# Base_Module.net
KiCad netlist of a schematic drawn in Altium Designer
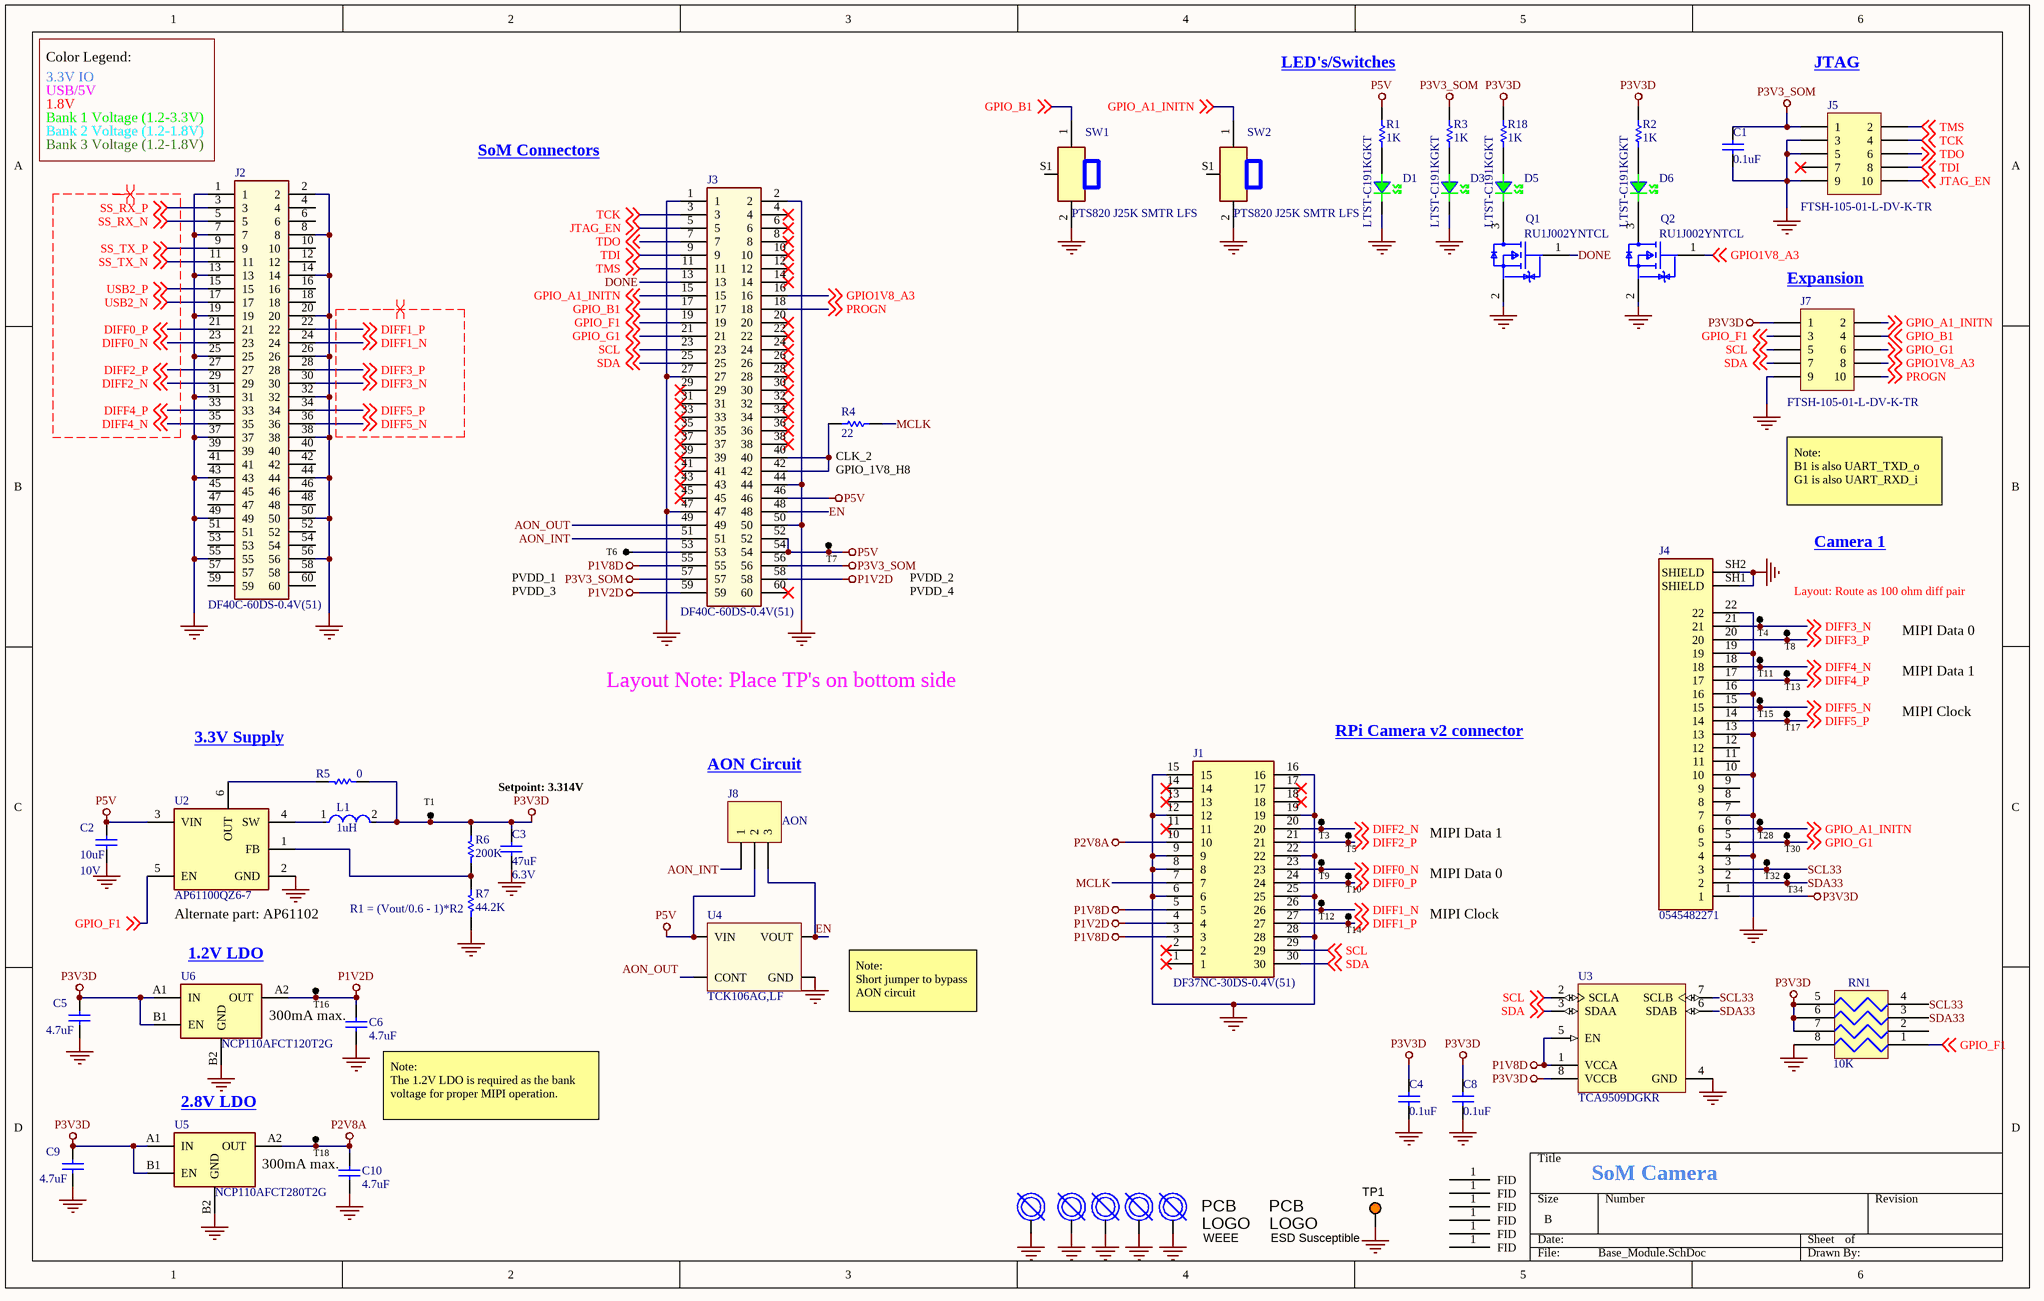
[diagram p0: Base_Module.SchDoc]

(export (version "E")
  (design (tool "Eeschema 10.0.6"))
  (components
    (comp (ref "BH1")
      (value "STANDOFF M2.5")
      (footprint "MH_Standoff_WE9774010151R")
      (description "RND STANDOFF M2.5X0.45 STEEL 1MM")
      (fields
        (field (name "MANUFACTURER") "Wurth Electronics")
        (field (name "MANUFACTURER PART NUMBER") "9774010151R")
      )
      (libsource (lib "MIPI_xlator") (part "MOUNT_HOLE"))
    )
    (comp (ref "BH2")
      (value "STANDOFF M2.5")
      (footprint "MH_Standoff_WE9774010151R")
      (description "RND STANDOFF M2.5X0.45 STEEL 1MM")
      (fields
        (field (name "MANUFACTURER") "Wurth Electronics")
        (field (name "MANUFACTURER PART NUMBER") "9774010151R")
      )
      (libsource (lib "MIPI_xlator") (part "MOUNT_HOLE"))
    )
    (comp (ref "BH3")
      (value "STANDOFF M2.5")
      (footprint "MH_Standoff_WE9774010151R")
      (description "RND STANDOFF M2.5X0.45 STEEL 1MM")
      (fields
        (field (name "MANUFACTURER") "Wurth Electronics")
        (field (name "MANUFACTURER PART NUMBER") "9774010151R")
      )
      (libsource (lib "MIPI_xlator") (part "MOUNT_HOLE"))
    )
    (comp (ref "BH4")
      (value "STANDOFF M2.5")
      (footprint "MH_Standoff_WE9774010151R")
      (description "RND STANDOFF M2.5X0.45 STEEL 1MM")
      (fields
        (field (name "MANUFACTURER") "Wurth Electronics")
        (field (name "MANUFACTURER PART NUMBER") "9774010151R")
      )
      (libsource (lib "MIPI_xlator") (part "MOUNT_HOLE"))
    )
    (comp (ref "BH5")
      (value "STANDOFF M2.5")
      (footprint "MH_3MM")
      (description "ROUND STANDOFF M2X0.4 STEEL 1MM")
      (libsource (lib "MIPI_xlator") (part "MOUNT_HOLE"))
    )
    (comp (ref "C1")
      (value "0.1uF")
      (footprint "CAPC1005X55USR")
      (description "CAP CER 0.1UF 16V X7R 0402")
      (fields
        (field (name "MANUFACTURER PART NUMBER") "CGA2B1X7R1C104K050BC")
        (field (name "MANUFACTURER") "TDK Corporation")
      )
      (libsource (lib "NX Module baseboard") (part "CAP CER 0.1UF 16V X7R 0402"))
    )
    (comp (ref "C2")
      (value "10uF")
      (footprint "CAP_0603")
      (description "CAP CER 10uF 10V X5R 0603")
      (fields
        (field (name "MANUFACTURER PART NUMBER") "GRM188R61A106ME69D")
        (field (name "MANUFACTURER") "Murata Electronics")
        (field (name "VOLTAGE") "10V")
      )
      (libsource (lib "Smart Camera") (part "Cap_1uF_X5R_10%_6V3_0402"))
    )
    (comp (ref "C3")
      (value "47uF")
      (footprint "CAP_0603")
      (description "CAP CER 47UF 6.3V X5R 0603")
      (fields
        (field (name "MANUFACTURER PART NUMBER") "GRM188R60J476ME15D")
        (field (name "MANUFACTURER") "Murata Electronics")
        (field (name "VOLTAGE") "6.3V")
      )
      (libsource (lib "Smart Camera") (part "Cap_1uF_X5R_10%_6V3_0402"))
    )
    (comp (ref "C4")
      (value "0.1uF")
      (footprint "CAPC1005X55USR")
      (description "CAP CER 0.1UF 16V X7R 0402")
      (fields
        (field (name "MANUFACTURER PART NUMBER") "CGA2B1X7R1C104K050BC")
        (field (name "MANUFACTURER") "TDK Corporation")
      )
      (libsource (lib "NX Module baseboard") (part "CAP CER 0.1UF 16V X7R 0402"))
    )
    (comp (ref "C5")
      (value "4.7uF")
      (footprint "CAPC1005X55USR")
      (description "CAP CER 4.7UF 10V X5R 0402")
      (fields
        (field (name "MANUFACTURER PART NUMBER") "C1005X5R1A475M050BC")
        (field (name "MANUFACTURER") "TDK Corporation")
      )
      (libsource (lib "NX Module baseboard") (part "CAP CER 4.7UF 10V X5R 0402"))
    )
    (comp (ref "C6")
      (value "4.7uF")
      (footprint "CAPC1005X55USR")
      (description "CAP CER 4.7UF 10V X5R 0402")
      (fields
        (field (name "MANUFACTURER PART NUMBER") "C1005X5R1A475M050BC")
        (field (name "MANUFACTURER") "TDK Corporation")
      )
      (libsource (lib "NX Module baseboard") (part "CAP CER 4.7UF 10V X5R 0402"))
    )
    (comp (ref "C8")
      (value "0.1uF")
      (footprint "CAPC1005X55USR")
      (description "CAP CER 0.1UF 16V X7R 0402")
      (fields
        (field (name "MANUFACTURER PART NUMBER") "CGA2B1X7R1C104K050BC")
        (field (name "MANUFACTURER") "TDK Corporation")
      )
      (libsource (lib "NX Module baseboard") (part "CAP CER 0.1UF 16V X7R 0402"))
    )
    (comp (ref "C9")
      (value "4.7uF")
      (footprint "CAPC1005X55USR")
      (description "CAP CER 4.7UF 10V X5R 0402")
      (fields
        (field (name "MANUFACTURER PART NUMBER") "C1005X5R1A475M050BC")
        (field (name "MANUFACTURER") "TDK Corporation")
      )
      (libsource (lib "NX Module baseboard") (part "CAP CER 4.7UF 10V X5R 0402"))
    )
    (comp (ref "C10")
      (value "4.7uF")
      (footprint "CAPC1005X55USR")
      (description "CAP CER 4.7UF 10V X5R 0402")
      (fields
        (field (name "MANUFACTURER PART NUMBER") "C1005X5R1A475M050BC")
        (field (name "MANUFACTURER") "TDK Corporation")
      )
      (libsource (lib "NX Module baseboard") (part "CAP CER 4.7UF 10V X5R 0402"))
    )
    (comp (ref "D1")
      (value "LTST-C191KGKT")
      (footprint "LED_0603")
      (description "LED GREEN CLEAR CHIP 0603 SMD")
      (fields
        (field (name "MANUFACTURER") "Lite-On Inc.")
        (field (name "MANUFACTURER PART NUMBER") "LTST-C191GKT")
      )
      (libsource (lib "Tiger_Ti180") (part "0603LED_GRN"))
    )
    (comp (ref "D3")
      (value "LTST-C191KGKT")
      (footprint "LED_0603")
      (description "LED GREEN CLEAR CHIP 0603 SMD")
      (fields
        (field (name "MANUFACTURER") "Lite-On Inc.")
        (field (name "MANUFACTURER PART NUMBER") "LTST-C191GKT")
      )
      (libsource (lib "Tiger_Ti180") (part "0603LED_GRN"))
    )
    (comp (ref "D5")
      (value "LTST-C191KGKT")
      (footprint "LED_0603")
      (description "LED GREEN CLEAR CHIP 0603 SMD")
      (fields
        (field (name "MANUFACTURER") "Lite-On Inc.")
        (field (name "MANUFACTURER PART NUMBER") "LTST-C191GKT")
      )
      (libsource (lib "Tiger_Ti180") (part "0603LED_GRN"))
    )
    (comp (ref "D6")
      (value "LTST-C191KGKT")
      (footprint "LED_0603")
      (description "LED GREEN CLEAR CHIP 0603 SMD")
      (fields
        (field (name "MANUFACTURER") "Lite-On Inc.")
        (field (name "MANUFACTURER PART NUMBER") "LTST-C191GKT")
      )
      (libsource (lib "Tiger_Ti180") (part "0603LED_GRN"))
    )
    (comp (ref "FID1") (value "~") (footprint "FID_040") (libsource (lib "MIPI_xlator") (part "FID")))
    (comp (ref "FID2") (value "~") (footprint "FID_040") (libsource (lib "MIPI_xlator") (part "FID")))
    (comp (ref "FID3") (value "~") (footprint "FID_040") (libsource (lib "MIPI_xlator") (part "FID")))
    (comp (ref "FID4") (value "~") (footprint "FID_040") (libsource (lib "MIPI_xlator") (part "FID")))
    (comp (ref "FID5") (value "~") (footprint "FID_040") (libsource (lib "MIPI_xlator") (part "FID")))
    (comp (ref "FID6") (value "~") (footprint "FID_040") (libsource (lib "MIPI_xlator") (part "FID")))
    (comp (ref "J1")
      (value "DF37NC-30DS-0.4V(51)")
      (footprint "HRS_DF37NC-30DS-0.4V(51)")
      (description "Conn Stacking RCP 30 POS 0.98mm Stack Height 0.4mm Solder ST SMD Emboss T/R")
      (fields (field (name "MANUFACTURER") "Hirose"))
      (libsource (lib "tinyCamera") (part "DF37NC-30DS-0.4V(51)"))
    )
    (comp (ref "J2")
      (value "DF40C-60DS-0.4V(51)")
      (footprint "DF40C60DS04V51")
      (description "CONN RCPT 60POS SMD GOLD")
      (fields (field (name "MANUFACTURER") "Hirose"))
      (libsource (lib "NX Module baseboard") (part "DF40C-60DS-0.4V(51)"))
    )
    (comp (ref "J3")
      (value "DF40C-60DS-0.4V(51)")
      (footprint "DF40C60DS04V51")
      (description "CONN RCPT 60POS SMD GOLD")
      (fields (field (name "MANUFACTURER") "Hirose"))
      (libsource (lib "NX Module baseboard") (part "DF40C-60DS-0.4V(51)"))
    )
    (comp (ref "J4")
      (value "0545482271")
      (footprint "MOLEX_54548-2271")
      (description "CONN FFC BOTTOM 22POS 0.50MM R/A")
      (fields (field (name "MANUFACTURER") "Molex"))
      (libsource (lib "tinyAI") (part "54548-2271"))
    )
    (comp (ref "J5")
      (value "FTSH-105-01-L-DV-K-TR")
      (footprint "FTSH-105-01-XXX-DV-K")
      (description "CONN HEADER SMD 10POS 1.27MM")
      (fields (field (name "MANUFACTURER") "Samtec Inc."))
      (libsource (lib "tinyAI") (part "HDR2X5_1.27mm"))
    )
    (comp (ref "J7")
      (value "FTSH-105-01-L-DV-K-TR")
      (footprint "FTSH-105-01-XXX-DV-K")
      (description "CONN HEADER SMD 10POS 1.27MM")
      (fields (field (name "MANUFACTURER") "Samtec Inc."))
      (libsource (lib "tinyAI") (part "HDR2X5_1.27mm"))
    )
    (comp (ref "J8")
      (value "AON")
      (footprint "HDR1X3")
      (description "CONN HEADER VERT 3POS 2.54MM")
      (fields
        (field (name "MANUFACTURER") "Wurth Electronics")
        (field (name "MANUFACTURER PART NUMBER") "61300311121")
      )
      (libsource (lib "Miscellaneous Connectors") (part "Header 3"))
    )
    (comp (ref "L1")
      (value "1uH")
      (footprint "INDC2016X100N")
      (description "FIXED IND 1UH 2.7A 57 MOHM SMD")
      (fields
        (field (name "MANUFACTURER") "Murata Electronics")
        (field (name "MANUFACTURER PART NUMBER") "DFE201610E-1R0M=P2")
      )
      (libsource (lib "Smart Camera") (part "725321dda6339637d4d059423bc1c3c"))
    )
    (comp (ref "Logo1")
      (value "WEEE")
      (footprint "WEEE_Minimum")
      (description "WEEE logo")
      (libsource (lib "MIPI_xlator") (part "Logo WEEE"))
    )
    (comp (ref "Logo2")
      (value "ESD Susceptible")
      (footprint "ESD_Overlay_Medium")
      (description "ESD Susceptible Symbol")
      (fields (field (name "PUBLISHER") "Texas Instruments") (field (name "SYMBOLCREATOR") "a0412235"))
      (libsource (lib "MIPI_xlator") (part "Logo ESD"))
    )
    (comp (ref "Q1")
      (value "RU1J002YNTCL")
      (footprint "SOT-323FL")
      (description "MOSFET N-CH 50V 0.2A UMT3F")
      (fields
        (field (name "MANUFACTURER") "Rohm")
        (field (name "OCTOPART") "https://octopart.com/ru1j002yntcl-rohm-47197697")
      )
      (libsource (lib "AiC") (part "1926738d861a973c8d722c53ec8fd09"))
    )
    (comp (ref "Q2")
      (value "RU1J002YNTCL")
      (footprint "SOT-323FL")
      (description "MOSFET N-CH 50V 0.2A UMT3F")
      (fields
        (field (name "MANUFACTURER") "Rohm")
        (field (name "OCTOPART") "https://octopart.com/ru1j002yntcl-rohm-47197697")
      )
      (libsource (lib "AiC") (part "1926738d861a973c8d722c53ec8fd09"))
    )
    (comp (ref "R1")
      (value "1K")
      (footprint "RESC1005X40USR")
      (description "RES SMD 1K OHM 1% 1/16W 0402")
      (fields
        (field (name "MANUFACTURER") "YAGEO")
        (field (name "MANUFACTURER PART NUMBER") "RC0402FR-071KL")
      )
      (libsource (lib "Tiger_Ti180") (part "RES 1K OHM 1% 1/16W 0402"))
    )
    (comp (ref "R2")
      (value "1K")
      (footprint "RESC1005X40USR")
      (description "RES SMD 1K OHM 1% 1/16W 0402")
      (fields
        (field (name "MANUFACTURER") "YAGEO")
        (field (name "MANUFACTURER PART NUMBER") "RC0402FR-071KL")
      )
      (libsource (lib "Tiger_Ti180") (part "RES 1K OHM 1% 1/16W 0402"))
    )
    (comp (ref "R3")
      (value "1K")
      (footprint "RESC1005X40USR")
      (description "RES SMD 1K OHM 1% 1/16W 0402")
      (fields
        (field (name "MANUFACTURER") "YAGEO")
        (field (name "MANUFACTURER PART NUMBER") "RC0402FR-071KL")
      )
      (libsource (lib "Tiger_Ti180") (part "RES 1K OHM 1% 1/16W 0402"))
    )
    (comp (ref "R4")
      (value "22")
      (footprint "RESC1005X40USR")
      (description "RES 22 OHM 1% 1/16W 0402")
      (fields
        (field (name "MANUFACTURER") "YAGEO")
        (field (name "MANUFACTURER PART NUMBER") "RC0402FR-0722RL")
      )
      (libsource (lib "Tiger_Ti180") (part "RES 1K OHM 1% 1/16W 0402"))
    )
    (comp (ref "R5")
      (value "0")
      (footprint "RESC1005X40USR")
      (description "RES 0 OHM JUMPER 1/16W 0402")
      (fields
        (field (name "MANUFACTURER") "Yageo")
        (field (name "MANUFACTURER PART NUMBER") "RC0402JR-070RL")
      )
      (libsource (lib "Smart Camera v2") (part "RES 0 OHM JUMPER 1/20W 0201"))
    )
    (comp (ref "R6")
      (value "200K")
      (footprint "RESC1005X40USR")
      (description "RES SMD 200K OHM 1% 1/16W 0402")
      (fields
        (field (name "MANUFACTURER") "Stackpole Electronics Inc")
        (field (name "MANUFACTURER PART NUMBER") "RMCF0402FT200K")
      )
      (libsource (lib "MCD_Temp_LBE") (part "Res_10K_1%_0402"))
    )
    (comp (ref "R7")
      (value "44.2K")
      (footprint "RESC1005X40USR")
      (description "RES SMD 44.2K OHM 1% 1/16W 0402")
      (fields
        (field (name "MANUFACTURER") "Yageo")
        (field (name "MANUFACTURER PART NUMBER") "RC0402FR-0744K2L")
      )
      (libsource (lib "MCD_Temp_LBE") (part "Res_10K_1%_0402"))
    )
    (comp (ref "R18")
      (value "1K")
      (footprint "RESC1005X40USR")
      (description "RES SMD 1K OHM 1% 1/16W 0402")
      (fields
        (field (name "MANUFACTURER") "YAGEO")
        (field (name "MANUFACTURER PART NUMBER") "RC0402FR-071KL")
      )
      (libsource (lib "Tiger_Ti180") (part "RES 1K OHM 1% 1/16W 0402"))
    )
    (comp (ref "RN1")
      (value "10K")
      (footprint "RESCAXS50P100X200X45-8NA")
      (description "Res Thick Film Array 10K Ohm 5% ±200ppm/°C ISOL 8-Pin 0804(4 X 0402) Convex SMD Automotive T/R")
      (fields
        (field (name "MANUFACTURER") "Panasonic")
        (field (name "MANUFACTURER PART NUMBER") "EXB-28V103JX")
      )
      (libsource (lib "NX Module") (part "RES ARRAY 4 RES 47K OHM 0804"))
    )
    (comp (ref "SW1")
      (value "PTS820 J25K SMTR LFS")
      (footprint "PTS820J25MSMTRLFS")
      (description "SWITCH TACTILE SPST-NO 0.05A 12V")
      (fields (field (name "MANUFACTURER") "C&K"))
      (libsource (lib "Tiger_Ti180") (part "SPST_NO"))
    )
    (comp (ref "SW2")
      (value "PTS820 J25K SMTR LFS")
      (footprint "PTS820J25MSMTRLFS")
      (description "SWITCH TACTILE SPST-NO 0.05A 12V")
      (fields (field (name "MANUFACTURER") "C&K"))
      (libsource (lib "Tiger_Ti180") (part "SPST_NO"))
    )
    (comp (ref "T1")
      (value "3V3")
      (footprint "TP 1mm")
      (description "test point")
      (libsource (lib "Smart Camera") (part "TP_S"))
    )
    (comp (ref "T3")
      (value "TP_S")
      (footprint "TP 20mil")
      (description "test point")
      (libsource (lib "AiC RVP Adapter") (part "TP_S"))
    )
    (comp (ref "T4")
      (value "TP_S")
      (footprint "TP 20mil")
      (description "test point")
      (libsource (lib "AiC RVP Adapter") (part "TP_S"))
    )
    (comp (ref "T5")
      (value "TP_S")
      (footprint "TP 20mil")
      (description "test point")
      (libsource (lib "AiC RVP Adapter") (part "TP_S"))
    )
    (comp (ref "T6")
      (value "TP_S")
      (footprint "TP 20mil")
      (description "test point")
      (libsource (lib "AiC RVP Adapter") (part "TP_S"))
    )
    (comp (ref "T7")
      (value "TP_S")
      (footprint "TP 20mil")
      (description "test point")
      (libsource (lib "AiC RVP Adapter") (part "TP_S"))
    )
    (comp (ref "T8")
      (value "TP_S")
      (footprint "TP 20mil")
      (description "test point")
      (libsource (lib "AiC RVP Adapter") (part "TP_S"))
    )
    (comp (ref "T9")
      (value "TP_S")
      (footprint "TP 20mil")
      (description "test point")
      (libsource (lib "AiC RVP Adapter") (part "TP_S"))
    )
    (comp (ref "T10")
      (value "TP_S")
      (footprint "TP 20mil")
      (description "test point")
      (libsource (lib "AiC RVP Adapter") (part "TP_S"))
    )
    (comp (ref "T11")
      (value "TP_S")
      (footprint "TP 20mil")
      (description "test point")
      (libsource (lib "AiC RVP Adapter") (part "TP_S"))
    )
    (comp (ref "T12")
      (value "TP_S")
      (footprint "TP 20mil")
      (description "test point")
      (libsource (lib "AiC RVP Adapter") (part "TP_S"))
    )
    (comp (ref "T13")
      (value "TP_S")
      (footprint "TP 20mil")
      (description "test point")
      (libsource (lib "AiC RVP Adapter") (part "TP_S"))
    )
    (comp (ref "T14")
      (value "TP_S")
      (footprint "TP 20mil")
      (description "test point")
      (libsource (lib "AiC RVP Adapter") (part "TP_S"))
    )
    (comp (ref "T15")
      (value "TP_S")
      (footprint "TP 20mil")
      (description "test point")
      (libsource (lib "AiC RVP Adapter") (part "TP_S"))
    )
    (comp (ref "T16")
      (value "TP_S")
      (footprint "TP 20mil")
      (description "test point")
      (libsource (lib "AiC RVP Adapter") (part "TP_S"))
    )
    (comp (ref "T17")
      (value "TP_S")
      (footprint "TP 20mil")
      (description "test point")
      (libsource (lib "AiC RVP Adapter") (part "TP_S"))
    )
    (comp (ref "T18")
      (value "TP_S")
      (footprint "TP 20mil")
      (description "test point")
      (libsource (lib "AiC RVP Adapter") (part "TP_S"))
    )
    (comp (ref "T28")
      (value "TP_S")
      (footprint "TP 20mil")
      (description "test point")
      (libsource (lib "AiC RVP Adapter") (part "TP_S"))
    )
    (comp (ref "T30")
      (value "TP_S")
      (footprint "TP 20mil")
      (description "test point")
      (libsource (lib "AiC RVP Adapter") (part "TP_S"))
    )
    (comp (ref "T32")
      (value "TP_S")
      (footprint "TP 1mm")
      (description "test point")
      (libsource (lib "tinyEye") (part "TP_S"))
    )
    (comp (ref "T34")
      (value "TP_S")
      (footprint "TP 1mm")
      (description "test point")
      (libsource (lib "tinyEye") (part "TP_S"))
    )
    (comp (ref "TP1")
      (value "5019")
      (footprint "TP380X203")
      (description "PC TEST POINT MINIATURE")
      (fields (field (name "MANUFACTURER") "Keystone Electronics"))
      (libsource (lib "MIPI_xlator") (part "5019"))
    )
    (comp (ref "U2")
      (value "AP61100QZ6-7")
      (footprint "SOTFL50P160X60-6N")
      (description "DC-DC CONV LV BUCK SOT563")
      (fields (field (name "MANUFACTURER") "Diodes Incorporated"))
      (libsource (lib "Smart Camera") (part "AP61100Z6-7"))
    )
    (comp (ref "U3")
      (value "TCA9509DGKR")
      (footprint "SOP65P490X110-8N")
      (description "Level-translating I2C And Smbus")
      (fields (field (name "MANUFACTURER") "Texas Instruments"))
      (libsource (lib "NX Module") (part "TI-TCA9509-MSOP_DGK-8"))
    )
    (comp (ref "U4")
      (value "TCK106AG,LF")
      (footprint "WCSP4D")
      (description "IC PWR SWITCH P-CHAN 1:1 4WCSPD")
      (fields
        (field (name "MANUFACTURER") "Toshiba")
        (field (name "COPYRIGHT") "Copyright (C) 2018 Accelerated Designs. All rights reserved")
      )
      (libsource (lib "tinyAI") (part "TCK106AG"))
    )
    (comp (ref "U5")
      (value "NCP110AFCT280T2G")
      (footprint "WLCSP4_P6XP6_ONS")
      (description "LDO Regulator, 200 mA, Low Vin, Ultra-High PSRR 2.8V, Active Discharge")
      (fields (field (name "MANUFACTURER") "ON Semiconductor"))
      (libsource (lib "Tiger_Ti180") (part "NCP110AFCT120T2G"))
    )
    (comp (ref "U6")
      (value "NCP110AFCT120T2G")
      (footprint "WLCSP4_P6XP6_ONS")
      (description "LDO Regulator, 200 mA, Low Vin, Ultra-High PSRR 1.2V, Active Discharge")
      (fields (field (name "MANUFACTURER") "ON Semiconductor"))
      (libsource (lib "Tiger_Ti180") (part "NCP110AFCT120T2G"))
    )
  )
  (nets
    (net (code "1") (name "/AON_INT") (class "Default")
      (node (ref "J3") (pin "51") (pinfunction "51_51") (pintype "passive"))
      (node (ref "J8") (pin "1") (pinfunction "1_1") (pintype "passive"))
    )
    (net (code "2") (name "/AON_OUT") (class "Default")
      (node (ref "J3") (pin "49") (pinfunction "49_49") (pintype "passive"))
      (node (ref "U4") (pin "B2") (pinfunction "CONT_B2") (pintype "passive"))
    )
    (net (code "3") (name "/DONE") (class "Default")
      (node (ref "J3") (pin "13") (pinfunction "13_13") (pintype "passive"))
      (node (ref "Q1") (pin "1") (pinfunction "G_1") (pintype "passive"))
    )
    (net (code "4") (name "/EN") (class "Default")
      (node (ref "J3") (pin "48") (pinfunction "48_48") (pintype "passive"))
      (node (ref "J8") (pin "3") (pinfunction "3_3") (pintype "passive"))
      (node (ref "U4") (pin "A1") (pinfunction "VOUT_A1") (pintype "passive"))
    )
    (net (code "5") (name "/MCLK") (class "Default")
      (node (ref "J1") (pin "7") (pinfunction "7_7") (pintype "passive"))
      (node (ref "R4") (pin "2") (pinfunction "2_2") (pintype "passive"))
    )
    (net (code "6") (name "/SCL33") (class "Default")
      (node (ref "J4") (pin "3") (pinfunction "3_3") (pintype "passive"))
      (node (ref "RN1") (pin "4") (pintype "passive"))
      (node (ref "T32") (pin "1") (pintype "passive"))
      (node (ref "U3") (pin "7") (pinfunction "SCLB_7") (pintype "bidirectional"))
    )
    (net (code "7") (name "/SDA33") (class "Default")
      (node (ref "J4") (pin "2") (pinfunction "2_2") (pintype "passive"))
      (node (ref "RN1") (pin "3") (pintype "passive"))
      (node (ref "T34") (pin "1") (pintype "passive"))
      (node (ref "U3") (pin "6") (pinfunction "SDAB_6") (pintype "bidirectional"))
    )
    (net (code "8") (name "DIFF0_N") (class "Default")
      (node (ref "J1") (pin "23") (pinfunction "23_23") (pintype "passive"))
      (node (ref "J2") (pin "23") (pinfunction "23_23") (pintype "passive"))
      (node (ref "T9") (pin "1") (pintype "passive"))
    )
    (net (code "9") (name "DIFF0_P") (class "Default")
      (node (ref "J1") (pin "24") (pinfunction "24_24") (pintype "passive"))
      (node (ref "J2") (pin "21") (pinfunction "21_21") (pintype "passive"))
      (node (ref "T10") (pin "1") (pintype "passive"))
    )
    (net (code "10") (name "DIFF1_N") (class "Default")
      (node (ref "J1") (pin "26") (pinfunction "26_26") (pintype "passive"))
      (node (ref "J2") (pin "24") (pinfunction "24_24") (pintype "passive"))
      (node (ref "T12") (pin "1") (pintype "passive"))
    )
    (net (code "11") (name "DIFF1_P") (class "Default")
      (node (ref "J1") (pin "27") (pinfunction "27_27") (pintype "passive"))
      (node (ref "J2") (pin "22") (pinfunction "22_22") (pintype "passive"))
      (node (ref "T14") (pin "1") (pintype "passive"))
    )
    (net (code "12") (name "DIFF2_N") (class "Default")
      (node (ref "J1") (pin "20") (pinfunction "20_20") (pintype "passive"))
      (node (ref "J2") (pin "29") (pinfunction "29_29") (pintype "passive"))
      (node (ref "T3") (pin "1") (pintype "passive"))
    )
    (net (code "13") (name "DIFF2_P") (class "Default")
      (node (ref "J1") (pin "21") (pinfunction "21_21") (pintype "passive"))
      (node (ref "J2") (pin "27") (pinfunction "27_27") (pintype "passive"))
      (node (ref "T5") (pin "1") (pintype "passive"))
    )
    (net (code "14") (name "DIFF3_N") (class "Default")
      (node (ref "J2") (pin "30") (pinfunction "30_30") (pintype "passive"))
      (node (ref "J4") (pin "21") (pinfunction "21_21") (pintype "passive"))
      (node (ref "T4") (pin "1") (pintype "passive"))
    )
    (net (code "15") (name "DIFF3_P") (class "Default")
      (node (ref "J2") (pin "28") (pinfunction "28_28") (pintype "passive"))
      (node (ref "J4") (pin "20") (pinfunction "20_20") (pintype "passive"))
      (node (ref "T8") (pin "1") (pintype "passive"))
    )
    (net (code "16") (name "DIFF4_N") (class "Default")
      (node (ref "J2") (pin "35") (pinfunction "35_35") (pintype "passive"))
      (node (ref "J4") (pin "18") (pinfunction "18_18") (pintype "passive"))
      (node (ref "T11") (pin "1") (pintype "passive"))
    )
    (net (code "17") (name "DIFF4_P") (class "Default")
      (node (ref "J2") (pin "33") (pinfunction "33_33") (pintype "passive"))
      (node (ref "J4") (pin "17") (pinfunction "17_17") (pintype "passive"))
      (node (ref "T13") (pin "1") (pintype "passive"))
    )
    (net (code "18") (name "DIFF5_N") (class "Default")
      (node (ref "J2") (pin "36") (pinfunction "36_36") (pintype "passive"))
      (node (ref "J4") (pin "15") (pinfunction "15_15") (pintype "passive"))
      (node (ref "T15") (pin "1") (pintype "passive"))
    )
    (net (code "19") (name "DIFF5_P") (class "Default")
      (node (ref "J2") (pin "34") (pinfunction "34_34") (pintype "passive"))
      (node (ref "J4") (pin "14") (pinfunction "14_14") (pintype "passive"))
      (node (ref "T17") (pin "1") (pintype "passive"))
    )
    (net (code "20") (name "GND") (class "Default")
      (node (ref "BH1") (pin "1") (pinfunction "1_1") (pintype "passive"))
      (node (ref "BH2") (pin "1") (pinfunction "1_1") (pintype "passive"))
      (node (ref "BH3") (pin "1") (pinfunction "1_1") (pintype "passive"))
      (node (ref "BH4") (pin "1") (pinfunction "1_1") (pintype "passive"))
      (node (ref "BH5") (pin "1") (pinfunction "1_1") (pintype "passive"))
      (node (ref "C1") (pin "1") (pinfunction "1_1") (pintype "passive"))
      (node (ref "C10") (pin "1") (pinfunction "1_1") (pintype "passive"))
      (node (ref "C2") (pin "1") (pinfunction "1_1") (pintype "passive"))
      (node (ref "C3") (pin "1") (pinfunction "1_1") (pintype "passive"))
      (node (ref "C4") (pin "1") (pinfunction "1_1") (pintype "passive"))
      (node (ref "C5") (pin "1") (pinfunction "1_1") (pintype "passive"))
      (node (ref "C6") (pin "1") (pinfunction "1_1") (pintype "passive"))
      (node (ref "C8") (pin "1") (pinfunction "1_1") (pintype "passive"))
      (node (ref "C9") (pin "1") (pinfunction "1_1") (pintype "passive"))
      (node (ref "D1") (pin "2") (pinfunction "K_2") (pintype "passive"))
      (node (ref "D3") (pin "2") (pinfunction "K_2") (pintype "passive"))
      (node (ref "J1") (pin "12") (pinfunction "12_12") (pintype "passive"))
      (node (ref "J1") (pin "15") (pinfunction "15_15") (pintype "passive"))
      (node (ref "J1") (pin "16") (pinfunction "16_16") (pintype "passive"))
      (node (ref "J1") (pin "19") (pinfunction "19_19") (pintype "passive"))
      (node (ref "J1") (pin "22") (pinfunction "22_22") (pintype "passive"))
      (node (ref "J1") (pin "25") (pinfunction "25_25") (pintype "passive"))
      (node (ref "J1") (pin "28") (pinfunction "28_28") (pintype "passive"))
      (node (ref "J1") (pin "6") (pinfunction "6_6") (pintype "passive"))
      (node (ref "J1") (pin "8") (pinfunction "8_8") (pintype "passive"))
      (node (ref "J1") (pin "9") (pinfunction "9_9") (pintype "passive"))
      (node (ref "J2") (pin "1") (pinfunction "1_1") (pintype "passive"))
      (node (ref "J2") (pin "13") (pinfunction "13_13") (pintype "passive"))
      (node (ref "J2") (pin "14") (pinfunction "14_14") (pintype "passive"))
      (node (ref "J2") (pin "19") (pinfunction "19_19") (pintype "passive"))
      (node (ref "J2") (pin "2") (pinfunction "2_2") (pintype "passive"))
      (node (ref "J2") (pin "20") (pinfunction "20_20") (pintype "passive"))
      (node (ref "J2") (pin "25") (pinfunction "25_25") (pintype "passive"))
      (node (ref "J2") (pin "26") (pinfunction "26_26") (pintype "passive"))
      (node (ref "J2") (pin "31") (pinfunction "31_31") (pintype "passive"))
      (node (ref "J2") (pin "32") (pinfunction "32_32") (pintype "passive"))
      (node (ref "J2") (pin "37") (pinfunction "37_37") (pintype "passive"))
      (node (ref "J2") (pin "38") (pinfunction "38_38") (pintype "passive"))
      (node (ref "J2") (pin "43") (pinfunction "43_43") (pintype "passive"))
      (node (ref "J2") (pin "44") (pinfunction "44_44") (pintype "passive"))
      (node (ref "J2") (pin "49") (pinfunction "49_49") (pintype "passive"))
      (node (ref "J2") (pin "50") (pinfunction "50_50") (pintype "passive"))
      (node (ref "J2") (pin "55") (pinfunction "55_55") (pintype "passive"))
      (node (ref "J2") (pin "56") (pinfunction "56_56") (pintype "passive"))
      (node (ref "J2") (pin "7") (pinfunction "7_7") (pintype "passive"))
      (node (ref "J2") (pin "8") (pinfunction "8_8") (pintype "passive"))
      (node (ref "J3") (pin "1") (pinfunction "1_1") (pintype "passive"))
      (node (ref "J3") (pin "2") (pinfunction "2_2") (pintype "passive"))
      (node (ref "J3") (pin "27") (pinfunction "27_27") (pintype "passive"))
      (node (ref "J3") (pin "44") (pinfunction "44_44") (pintype "passive"))
      (node (ref "J3") (pin "47") (pinfunction "47_47") (pintype "passive"))
      (node (ref "J3") (pin "50") (pinfunction "50_50") (pintype "passive"))
      (node (ref "J4") (pin "10") (pinfunction "10_10") (pintype "passive"))
      (node (ref "J4") (pin "13") (pinfunction "13_13") (pintype "passive"))
      (node (ref "J4") (pin "16") (pinfunction "16_16") (pintype "passive"))
      (node (ref "J4") (pin "19") (pinfunction "19_19") (pintype "passive"))
      (node (ref "J4") (pin "22") (pinfunction "22_22") (pintype "passive"))
      (node (ref "J4") (pin "4") (pinfunction "4_4") (pintype "passive"))
      (node (ref "J4") (pin "7") (pinfunction "7_7") (pintype "passive"))
      (node (ref "J4") (pin "SH1") (pinfunction "SHIELD_SH1") (pintype "passive"))
      (node (ref "J4") (pin "SH2") (pinfunction "SHIELD_SH2") (pintype "passive"))
      (node (ref "J5") (pin "3") (pinfunction "3_3") (pintype "passive"))
      (node (ref "J5") (pin "5") (pinfunction "5_5") (pintype "passive"))
      (node (ref "J5") (pin "9") (pinfunction "9_9") (pintype "passive"))
      (node (ref "J7") (pin "9") (pinfunction "9_9") (pintype "passive"))
      (node (ref "Q1") (pin "2") (pinfunction "S_2") (pintype "passive"))
      (node (ref "Q2") (pin "2") (pinfunction "S_2") (pintype "passive"))
      (node (ref "R7") (pin "1") (pinfunction "1_1") (pintype "passive"))
      (node (ref "RN1") (pin "8") (pintype "passive"))
      (node (ref "SW1") (pin "2") (pinfunction "2_2") (pintype "passive"))
      (node (ref "SW2") (pin "2") (pinfunction "2_2") (pintype "passive"))
      (node (ref "TP1") (pin "1") (pinfunction "1_1") (pintype "passive"))
      (node (ref "U2") (pin "2") (pinfunction "GND_2") (pintype "passive"))
      (node (ref "U3") (pin "4") (pinfunction "GND_4") (pintype "power_in"))
      (node (ref "U4") (pin "B1") (pinfunction "GND_B1") (pintype "passive"))
      (node (ref "U5") (pin "B2") (pinfunction "GND_B2") (pintype "passive"))
      (node (ref "U6") (pin "B2") (pinfunction "GND_B2") (pintype "passive"))
    )
    (net (code "21") (name "GPIO1V8_A3") (class "Default")
      (node (ref "J3") (pin "16") (pinfunction "16_16") (pintype "passive"))
      (node (ref "J7") (pin "8") (pinfunction "8_8") (pintype "passive"))
      (node (ref "Q2") (pin "1") (pinfunction "G_1") (pintype "passive"))
    )
    (net (code "22") (name "GPIO_A1_INITN") (class "Default")
      (node (ref "J3") (pin "15") (pinfunction "15_15") (pintype "passive"))
      (node (ref "J4") (pin "6") (pinfunction "6_6") (pintype "passive"))
      (node (ref "J7") (pin "2") (pinfunction "2_2") (pintype "passive"))
      (node (ref "SW2") (pin "1") (pinfunction "1_1") (pintype "passive"))
      (node (ref "T28") (pin "1") (pintype "passive"))
    )
    (net (code "23") (name "GPIO_B1") (class "Default")
      (node (ref "J3") (pin "17") (pinfunction "17_17") (pintype "passive"))
      (node (ref "J7") (pin "4") (pinfunction "4_4") (pintype "passive"))
      (node (ref "SW1") (pin "1") (pinfunction "1_1") (pintype "passive"))
    )
    (net (code "24") (name "GPIO_F1") (class "Default")
      (node (ref "J3") (pin "19") (pinfunction "19_19") (pintype "passive"))
      (node (ref "J7") (pin "3") (pinfunction "3_3") (pintype "passive"))
      (node (ref "RN1") (pin "1") (pintype "passive"))
      (node (ref "U2") (pin "5") (pinfunction "EN_5") (pintype "passive"))
    )
    (net (code "25") (name "GPIO_G1") (class "Default")
      (node (ref "J3") (pin "21") (pinfunction "21_21") (pintype "passive"))
      (node (ref "J4") (pin "5") (pinfunction "5_5") (pintype "passive"))
      (node (ref "J7") (pin "6") (pinfunction "6_6") (pintype "passive"))
      (node (ref "T30") (pin "1") (pintype "passive"))
    )
    (net (code "26") (name "JTAG_EN") (class "Default")
      (node (ref "J3") (pin "5") (pinfunction "5_5") (pintype "passive"))
      (node (ref "J5") (pin "10") (pinfunction "10_10") (pintype "passive"))
    )
    (net (code "27") (name "Net-(D1-A)") (class "Default")
      (node (ref "D1") (pin "1") (pinfunction "A_1") (pintype "passive"))
      (node (ref "R1") (pin "2") (pinfunction "2_2") (pintype "passive"))
    )
    (net (code "28") (name "Net-(D3-A)") (class "Default")
      (node (ref "D3") (pin "1") (pinfunction "A_1") (pintype "passive"))
      (node (ref "R3") (pin "2") (pinfunction "2_2") (pintype "passive"))
    )
    (net (code "29") (name "Net-(D5-A)") (class "Default")
      (node (ref "D5") (pin "1") (pinfunction "A_1") (pintype "passive"))
      (node (ref "R18") (pin "2") (pinfunction "2_2") (pintype "passive"))
    )
    (net (code "30") (name "Net-(D5-K)") (class "Default")
      (node (ref "D5") (pin "2") (pinfunction "K_2") (pintype "passive"))
      (node (ref "Q1") (pin "3") (pinfunction "D_3") (pintype "passive"))
    )
    (net (code "31") (name "Net-(D6-A)") (class "Default")
      (node (ref "D6") (pin "1") (pinfunction "A_1") (pintype "passive"))
      (node (ref "R2") (pin "2") (pinfunction "2_2") (pintype "passive"))
    )
    (net (code "32") (name "Net-(D6-K)") (class "Default")
      (node (ref "D6") (pin "2") (pinfunction "K_2") (pintype "passive"))
      (node (ref "Q2") (pin "3") (pinfunction "D_3") (pintype "passive"))
    )
    (net (code "33") (name "Net-(J3-Pad40)") (class "Default")
      (node (ref "J3") (pin "40") (pinfunction "40_40") (pintype "passive"))
      (node (ref "J3") (pin "42") (pinfunction "42_42") (pintype "passive"))
      (node (ref "R4") (pin "1") (pinfunction "1_1") (pintype "passive"))
    )
    (net (code "34") (name "Net-(J3-Pad53)") (class "Default")
      (node (ref "J3") (pin "53") (pinfunction "53_53") (pintype "passive"))
      (node (ref "T6") (pin "1") (pintype "passive"))
    )
    (net (code "35") (name "Net-(U2-FB)") (class "Default")
      (node (ref "R6") (pin "1") (pinfunction "1_1") (pintype "passive"))
      (node (ref "R7") (pin "2") (pinfunction "2_2") (pintype "passive"))
      (node (ref "U2") (pin "1") (pinfunction "FB_1") (pintype "passive"))
    )
    (net (code "36") (name "Net-(U2-OUT)") (class "Default")
      (node (ref "R5") (pin "2") (pinfunction "2_2") (pintype "passive"))
      (node (ref "U2") (pin "6") (pinfunction "OUT_6") (pintype "passive"))
    )
    (net (code "37") (name "Net-(U2-SW)") (class "Default")
      (node (ref "L1") (pin "1") (pinfunction "1_1") (pintype "passive"))
      (node (ref "U2") (pin "4") (pinfunction "SW_4") (pintype "passive"))
    )
    (net (code "38") (name "P1V2D") (class "Default")
      (node (ref "C6") (pin "2") (pinfunction "2_2") (pintype "passive"))
      (node (ref "J1") (pin "4") (pinfunction "4_4") (pintype "passive"))
      (node (ref "J3") (pin "58") (pinfunction "58_58") (pintype "passive"))
      (node (ref "J3") (pin "59") (pinfunction "59_59") (pintype "passive"))
      (node (ref "T16") (pin "1") (pintype "passive"))
      (node (ref "U6") (pin "A2") (pinfunction "OUT_A2") (pintype "passive"))
    )
    (net (code "39") (name "P1V8D") (class "Default")
      (node (ref "J1") (pin "3") (pinfunction "3_3") (pintype "passive"))
      (node (ref "J1") (pin "5") (pinfunction "5_5") (pintype "passive"))
      (node (ref "J3") (pin "55") (pinfunction "55_55") (pintype "passive"))
      (node (ref "U3") (pin "1") (pinfunction "VCCA_1") (pintype "power_in"))
      (node (ref "U3") (pin "5") (pinfunction "EN_5") (pintype "input"))
    )
    (net (code "40") (name "P2V8A") (class "Default")
      (node (ref "C10") (pin "2") (pinfunction "2_2") (pintype "passive"))
      (node (ref "J1") (pin "10") (pinfunction "10_10") (pintype "passive"))
      (node (ref "T18") (pin "1") (pintype "passive"))
      (node (ref "U5") (pin "A2") (pinfunction "OUT_A2") (pintype "passive"))
    )
    (net (code "41") (name "P3V3D") (class "Default")
      (node (ref "C3") (pin "2") (pinfunction "2_2") (pintype "passive"))
      (node (ref "C4") (pin "2") (pinfunction "2_2") (pintype "passive"))
      (node (ref "C5") (pin "2") (pinfunction "2_2") (pintype "passive"))
      (node (ref "C8") (pin "2") (pinfunction "2_2") (pintype "passive"))
      (node (ref "C9") (pin "2") (pinfunction "2_2") (pintype "passive"))
      (node (ref "J4") (pin "1") (pinfunction "1_1") (pintype "passive"))
      (node (ref "J7") (pin "1") (pinfunction "1_1") (pintype "passive"))
      (node (ref "L1") (pin "2") (pinfunction "2_2") (pintype "passive"))
      (node (ref "R18") (pin "1") (pinfunction "1_1") (pintype "passive"))
      (node (ref "R2") (pin "1") (pinfunction "1_1") (pintype "passive"))
      (node (ref "R5") (pin "1") (pinfunction "1_1") (pintype "passive"))
      (node (ref "R6") (pin "2") (pinfunction "2_2") (pintype "passive"))
      (node (ref "RN1") (pin "5") (pintype "passive"))
      (node (ref "RN1") (pin "6") (pintype "passive"))
      (node (ref "RN1") (pin "7") (pintype "passive"))
      (node (ref "T1") (pin "1") (pintype "passive"))
      (node (ref "U3") (pin "8") (pinfunction "VCCB_8") (pintype "power_in"))
      (node (ref "U5") (pin "A1") (pinfunction "IN_A1") (pintype "passive"))
      (node (ref "U5") (pin "B1") (pinfunction "EN_B1") (pintype "passive"))
      (node (ref "U6") (pin "A1") (pinfunction "IN_A1") (pintype "passive"))
      (node (ref "U6") (pin "B1") (pinfunction "EN_B1") (pintype "passive"))
    )
    (net (code "42") (name "P3V3_SOM") (class "Default")
      (node (ref "C1") (pin "2") (pinfunction "2_2") (pintype "passive"))
      (node (ref "J3") (pin "56") (pinfunction "56_56") (pintype "passive"))
      (node (ref "J3") (pin "57") (pinfunction "57_57") (pintype "passive"))
      (node (ref "J5") (pin "1") (pinfunction "1_1") (pintype "passive"))
      (node (ref "R3") (pin "1") (pinfunction "1_1") (pintype "passive"))
    )
    (net (code "43") (name "P5V") (class "Default")
      (node (ref "C2") (pin "2") (pinfunction "2_2") (pintype "passive"))
      (node (ref "J3") (pin "46") (pinfunction "46_46") (pintype "passive"))
      (node (ref "J3") (pin "52") (pinfunction "52_52") (pintype "passive"))
      (node (ref "J3") (pin "54") (pinfunction "54_54") (pintype "passive"))
      (node (ref "J8") (pin "2") (pinfunction "2_2") (pintype "passive"))
      (node (ref "R1") (pin "1") (pinfunction "1_1") (pintype "passive"))
      (node (ref "T7") (pin "1") (pintype "passive"))
      (node (ref "U2") (pin "3") (pinfunction "VIN_3") (pintype "passive"))
      (node (ref "U4") (pin "A2") (pinfunction "VIN_A2") (pintype "passive"))
    )
    (net (code "44") (name "PROGN") (class "Default")
      (node (ref "J3") (pin "18") (pinfunction "18_18") (pintype "passive"))
      (node (ref "J7") (pin "10") (pinfunction "10_10") (pintype "passive"))
    )
    (net (code "45") (name "SCL") (class "Default")
      (node (ref "J1") (pin "29") (pinfunction "29_29") (pintype "passive"))
      (node (ref "J3") (pin "23") (pinfunction "23_23") (pintype "passive"))
      (node (ref "J7") (pin "5") (pinfunction "5_5") (pintype "passive"))
      (node (ref "U3") (pin "2") (pinfunction "SCLA_2") (pintype "bidirectional"))
    )
    (net (code "46") (name "SDA") (class "Default")
      (node (ref "J1") (pin "30") (pinfunction "30_30") (pintype "passive"))
      (node (ref "J3") (pin "25") (pinfunction "25_25") (pintype "passive"))
      (node (ref "J7") (pin "7") (pinfunction "7_7") (pintype "passive"))
      (node (ref "U3") (pin "3") (pinfunction "SDAA_3") (pintype "bidirectional"))
    )
    (net (code "47") (name "SS_RX_N") (class "Default")
      (node (ref "J2") (pin "5") (pinfunction "5_5") (pintype "passive"))
    )
    (net (code "48") (name "SS_RX_P") (class "Default")
      (node (ref "J2") (pin "3") (pinfunction "3_3") (pintype "passive"))
    )
    (net (code "49") (name "SS_TX_N") (class "Default")
      (node (ref "J2") (pin "11") (pinfunction "11_11") (pintype "passive"))
    )
    (net (code "50") (name "SS_TX_P") (class "Default")
      (node (ref "J2") (pin "9") (pinfunction "9_9") (pintype "passive"))
    )
    (net (code "51") (name "TCK") (class "Default")
      (node (ref "J3") (pin "3") (pinfunction "3_3") (pintype "passive"))
      (node (ref "J5") (pin "4") (pinfunction "4_4") (pintype "passive"))
    )
    (net (code "52") (name "TDI") (class "Default")
      (node (ref "J3") (pin "9") (pinfunction "9_9") (pintype "passive"))
      (node (ref "J5") (pin "8") (pinfunction "8_8") (pintype "passive"))
    )
    (net (code "53") (name "TDO") (class "Default")
      (node (ref "J3") (pin "7") (pinfunction "7_7") (pintype "passive"))
      (node (ref "J5") (pin "6") (pinfunction "6_6") (pintype "passive"))
    )
    (net (code "54") (name "TMS") (class "Default")
      (node (ref "J3") (pin "11") (pinfunction "11_11") (pintype "passive"))
      (node (ref "J5") (pin "2") (pinfunction "2_2") (pintype "passive"))
    )
    (net (code "55") (name "USB2_N") (class "Default")
      (node (ref "J2") (pin "17") (pinfunction "17_17") (pintype "passive"))
    )
    (net (code "56") (name "USB2_P") (class "Default")
      (node (ref "J2") (pin "15") (pinfunction "15_15") (pintype "passive"))
    )
    (net (code "57") (name "unconnected-(FID1-FID-Pad1)") (class "Default")
      (node (ref "FID1") (pin "1") (pinfunction "FID_1") (pintype "passive"))
    )
    (net (code "58") (name "unconnected-(FID2-FID-Pad1)") (class "Default")
      (node (ref "FID2") (pin "1") (pinfunction "FID_1") (pintype "passive"))
    )
    (net (code "59") (name "unconnected-(FID3-FID-Pad1)") (class "Default")
      (node (ref "FID3") (pin "1") (pinfunction "FID_1") (pintype "passive"))
    )
    (net (code "60") (name "unconnected-(FID4-FID-Pad1)") (class "Default")
      (node (ref "FID4") (pin "1") (pinfunction "FID_1") (pintype "passive"))
    )
    (net (code "61") (name "unconnected-(FID5-FID-Pad1)") (class "Default")
      (node (ref "FID5") (pin "1") (pinfunction "FID_1") (pintype "passive"))
    )
    (net (code "62") (name "unconnected-(FID6-FID-Pad1)") (class "Default")
      (node (ref "FID6") (pin "1") (pinfunction "FID_1") (pintype "passive"))
    )
    (net (code "63") (name "unconnected-(J1-Pad1)") (class "Default")
      (node (ref "J1") (pin "1") (pinfunction "1_1") (pintype "passive+no_connect"))
    )
    (net (code "64") (name "unconnected-(J1-Pad2)") (class "Default")
      (node (ref "J1") (pin "2") (pinfunction "2_2") (pintype "passive+no_connect"))
    )
    (net (code "65") (name "unconnected-(J1-Pad11)") (class "Default")
      (node (ref "J1") (pin "11") (pinfunction "11_11") (pintype "passive+no_connect"))
    )
    (net (code "66") (name "unconnected-(J1-Pad13)") (class "Default")
      (node (ref "J1") (pin "13") (pinfunction "13_13") (pintype "passive+no_connect"))
    )
    (net (code "67") (name "unconnected-(J1-Pad14)") (class "Default")
      (node (ref "J1") (pin "14") (pinfunction "14_14") (pintype "passive+no_connect"))
    )
    (net (code "68") (name "unconnected-(J1-Pad17)") (class "Default")
      (node (ref "J1") (pin "17") (pinfunction "17_17") (pintype "passive+no_connect"))
    )
    (net (code "69") (name "unconnected-(J1-Pad18)") (class "Default")
      (node (ref "J1") (pin "18") (pinfunction "18_18") (pintype "passive+no_connect"))
    )
    (net (code "70") (name "unconnected-(J2-Pad4)") (class "Default")
      (node (ref "J2") (pin "4") (pinfunction "4_4") (pintype "passive"))
    )
    (net (code "71") (name "unconnected-(J2-Pad6)") (class "Default")
      (node (ref "J2") (pin "6") (pinfunction "6_6") (pintype "passive"))
    )
    (net (code "72") (name "unconnected-(J2-Pad10)") (class "Default")
      (node (ref "J2") (pin "10") (pinfunction "10_10") (pintype "passive"))
    )
    (net (code "73") (name "unconnected-(J2-Pad12)") (class "Default")
      (node (ref "J2") (pin "12") (pinfunction "12_12") (pintype "passive"))
    )
    (net (code "74") (name "unconnected-(J2-Pad16)") (class "Default")
      (node (ref "J2") (pin "16") (pinfunction "16_16") (pintype "passive"))
    )
    (net (code "75") (name "unconnected-(J2-Pad18)") (class "Default")
      (node (ref "J2") (pin "18") (pinfunction "18_18") (pintype "passive"))
    )
    (net (code "76") (name "unconnected-(J2-Pad39)") (class "Default")
      (node (ref "J2") (pin "39") (pinfunction "39_39") (pintype "passive"))
    )
    (net (code "77") (name "unconnected-(J2-Pad40)") (class "Default")
      (node (ref "J2") (pin "40") (pinfunction "40_40") (pintype "passive"))
    )
    (net (code "78") (name "unconnected-(J2-Pad41)") (class "Default")
      (node (ref "J2") (pin "41") (pinfunction "41_41") (pintype "passive"))
    )
    (net (code "79") (name "unconnected-(J2-Pad42)") (class "Default")
      (node (ref "J2") (pin "42") (pinfunction "42_42") (pintype "passive"))
    )
    (net (code "80") (name "unconnected-(J2-Pad45)") (class "Default")
      (node (ref "J2") (pin "45") (pinfunction "45_45") (pintype "passive"))
    )
    (net (code "81") (name "unconnected-(J2-Pad46)") (class "Default")
      (node (ref "J2") (pin "46") (pinfunction "46_46") (pintype "passive"))
    )
    (net (code "82") (name "unconnected-(J2-Pad47)") (class "Default")
      (node (ref "J2") (pin "47") (pinfunction "47_47") (pintype "passive"))
    )
    (net (code "83") (name "unconnected-(J2-Pad48)") (class "Default")
      (node (ref "J2") (pin "48") (pinfunction "48_48") (pintype "passive"))
    )
    (net (code "84") (name "unconnected-(J2-Pad51)") (class "Default")
      (node (ref "J2") (pin "51") (pinfunction "51_51") (pintype "passive"))
    )
    (net (code "85") (name "unconnected-(J2-Pad52)") (class "Default")
      (node (ref "J2") (pin "52") (pinfunction "52_52") (pintype "passive"))
    )
    (net (code "86") (name "unconnected-(J2-Pad53)") (class "Default")
      (node (ref "J2") (pin "53") (pinfunction "53_53") (pintype "passive"))
    )
    (net (code "87") (name "unconnected-(J2-Pad54)") (class "Default")
      (node (ref "J2") (pin "54") (pinfunction "54_54") (pintype "passive"))
    )
    (net (code "88") (name "unconnected-(J2-Pad57)") (class "Default")
      (node (ref "J2") (pin "57") (pinfunction "57_57") (pintype "passive"))
    )
    (net (code "89") (name "unconnected-(J2-Pad58)") (class "Default")
      (node (ref "J2") (pin "58") (pinfunction "58_58") (pintype "passive"))
    )
    (net (code "90") (name "unconnected-(J2-Pad59)") (class "Default")
      (node (ref "J2") (pin "59") (pinfunction "59_59") (pintype "passive"))
    )
    (net (code "91") (name "unconnected-(J2-Pad60)") (class "Default")
      (node (ref "J2") (pin "60") (pinfunction "60_60") (pintype "passive"))
    )
    (net (code "92") (name "unconnected-(J3-Pad4)") (class "Default")
      (node (ref "J3") (pin "4") (pinfunction "4_4") (pintype "passive+no_connect"))
    )
    (net (code "93") (name "unconnected-(J3-Pad6)") (class "Default")
      (node (ref "J3") (pin "6") (pinfunction "6_6") (pintype "passive+no_connect"))
    )
    (net (code "94") (name "unconnected-(J3-Pad8)") (class "Default")
      (node (ref "J3") (pin "8") (pinfunction "8_8") (pintype "passive+no_connect"))
    )
    (net (code "95") (name "unconnected-(J3-Pad10)") (class "Default")
      (node (ref "J3") (pin "10") (pinfunction "10_10") (pintype "passive+no_connect"))
    )
    (net (code "96") (name "unconnected-(J3-Pad12)") (class "Default")
      (node (ref "J3") (pin "12") (pinfunction "12_12") (pintype "passive+no_connect"))
    )
    (net (code "97") (name "unconnected-(J3-Pad14)") (class "Default")
      (node (ref "J3") (pin "14") (pinfunction "14_14") (pintype "passive+no_connect"))
    )
    (net (code "98") (name "unconnected-(J3-Pad20)") (class "Default")
      (node (ref "J3") (pin "20") (pinfunction "20_20") (pintype "passive+no_connect"))
    )
    (net (code "99") (name "unconnected-(J3-Pad22)") (class "Default")
      (node (ref "J3") (pin "22") (pinfunction "22_22") (pintype "passive+no_connect"))
    )
    (net (code "100") (name "unconnected-(J3-Pad24)") (class "Default")
      (node (ref "J3") (pin "24") (pinfunction "24_24") (pintype "passive+no_connect"))
    )
    (net (code "101") (name "unconnected-(J3-Pad26)") (class "Default")
      (node (ref "J3") (pin "26") (pinfunction "26_26") (pintype "passive+no_connect"))
    )
    (net (code "102") (name "unconnected-(J3-Pad28)") (class "Default")
      (node (ref "J3") (pin "28") (pinfunction "28_28") (pintype "passive+no_connect"))
    )
    (net (code "103") (name "unconnected-(J3-Pad29)") (class "Default")
      (node (ref "J3") (pin "29") (pinfunction "29_29") (pintype "passive+no_connect"))
    )
    (net (code "104") (name "unconnected-(J3-Pad30)") (class "Default")
      (node (ref "J3") (pin "30") (pinfunction "30_30") (pintype "passive+no_connect"))
    )
    (net (code "105") (name "unconnected-(J3-Pad31)") (class "Default")
      (node (ref "J3") (pin "31") (pinfunction "31_31") (pintype "passive+no_connect"))
    )
    (net (code "106") (name "unconnected-(J3-Pad32)") (class "Default")
      (node (ref "J3") (pin "32") (pinfunction "32_32") (pintype "passive+no_connect"))
    )
    (net (code "107") (name "unconnected-(J3-Pad33)") (class "Default")
      (node (ref "J3") (pin "33") (pinfunction "33_33") (pintype "passive+no_connect"))
    )
    (net (code "108") (name "unconnected-(J3-Pad34)") (class "Default")
      (node (ref "J3") (pin "34") (pinfunction "34_34") (pintype "passive+no_connect"))
    )
    (net (code "109") (name "unconnected-(J3-Pad35)") (class "Default")
      (node (ref "J3") (pin "35") (pinfunction "35_35") (pintype "passive+no_connect"))
    )
    (net (code "110") (name "unconnected-(J3-Pad36)") (class "Default")
      (node (ref "J3") (pin "36") (pinfunction "36_36") (pintype "passive+no_connect"))
    )
    (net (code "111") (name "unconnected-(J3-Pad37)") (class "Default")
      (node (ref "J3") (pin "37") (pinfunction "37_37") (pintype "passive+no_connect"))
    )
    (net (code "112") (name "unconnected-(J3-Pad38)") (class "Default")
      (node (ref "J3") (pin "38") (pinfunction "38_38") (pintype "passive+no_connect"))
    )
    (net (code "113") (name "unconnected-(J3-Pad39)") (class "Default")
      (node (ref "J3") (pin "39") (pinfunction "39_39") (pintype "passive+no_connect"))
    )
    (net (code "114") (name "unconnected-(J3-Pad41)") (class "Default")
      (node (ref "J3") (pin "41") (pinfunction "41_41") (pintype "passive+no_connect"))
    )
    (net (code "115") (name "unconnected-(J3-Pad43)") (class "Default")
      (node (ref "J3") (pin "43") (pinfunction "43_43") (pintype "passive+no_connect"))
    )
    (net (code "116") (name "unconnected-(J3-Pad45)") (class "Default")
      (node (ref "J3") (pin "45") (pinfunction "45_45") (pintype "passive+no_connect"))
    )
    (net (code "117") (name "unconnected-(J3-Pad60)") (class "Default")
      (node (ref "J3") (pin "60") (pinfunction "60_60") (pintype "passive+no_connect"))
    )
    (net (code "118") (name "unconnected-(J4-Pad8)") (class "Default")
      (node (ref "J4") (pin "8") (pinfunction "8_8") (pintype "passive"))
    )
    (net (code "119") (name "unconnected-(J4-Pad9)") (class "Default")
      (node (ref "J4") (pin "9") (pinfunction "9_9") (pintype "passive"))
    )
    (net (code "120") (name "unconnected-(J4-Pad11)") (class "Default")
      (node (ref "J4") (pin "11") (pinfunction "11_11") (pintype "passive"))
    )
    (net (code "121") (name "unconnected-(J4-Pad12)") (class "Default")
      (node (ref "J4") (pin "12") (pinfunction "12_12") (pintype "passive"))
    )
    (net (code "122") (name "unconnected-(J5-Pad7)") (class "Default")
      (node (ref "J5") (pin "7") (pinfunction "7_7") (pintype "passive+no_connect"))
    )
    (net (code "123") (name "unconnected-(RN1-Pad2)") (class "Default")
      (node (ref "RN1") (pin "2") (pintype "passive"))
    )
    (net (code "124") (name "unconnected-(SW1-GND-PadS1)") (class "Default")
      (node (ref "SW1") (pin "S1") (pinfunction "GND_S1") (pintype "passive"))
    )
    (net (code "125") (name "unconnected-(SW2-GND-PadS1)") (class "Default")
      (node (ref "SW2") (pin "S1") (pinfunction "GND_S1") (pintype "passive"))
    )
  )
)
